# Motor_Controller_STM32.net
KiCad netlist of a schematic drawn in EasyEDA Pro
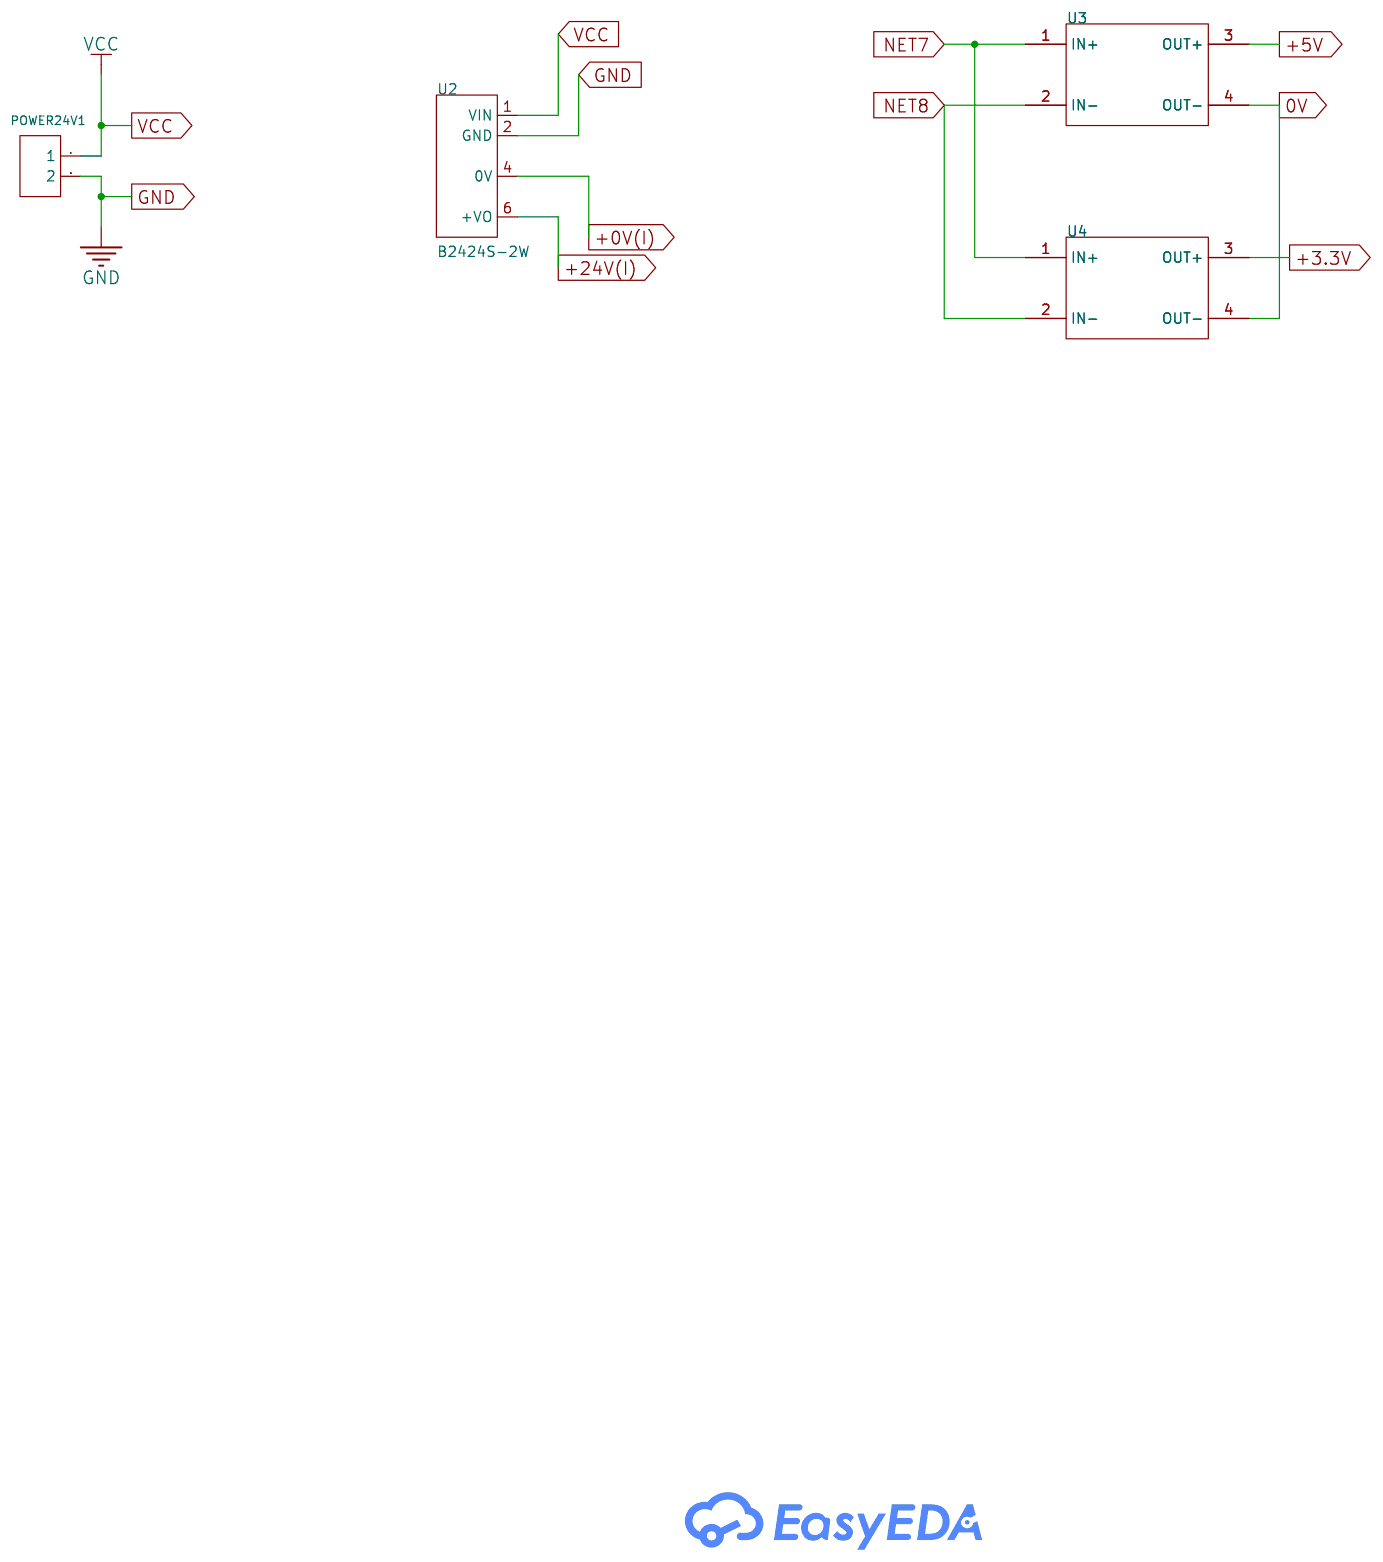
[diagram p0: schematic sheet]

(export (version "E")
  (design (tool "Eeschema 10.0.6"))
  (components
    (comp (ref "POWER24V1")
      (value "~")
      (footprint "easyedapro:HDR-TH_2P-P2.54-V-F")
      (libsource (lib "easyedapro") (part "Header-Female-2.54_1x2"))
    )
    (comp (ref "U2")
      (value "B2424S-2W")
      (footprint "easyedapro:PWRM-TH_BXXXXS-2W")
      (fields (field (name "Manufacturer") "JETEKPS(健特)"))
      (libsource (lib "easyedapro") (part "B2424S-2W_C442555"))
    )
    (comp (ref "U3")
      (value "~")
      (footprint "easyedapro:MINI 360")
      (libsource (lib "easyedapro") (part "Buck Converter Mini 360"))
    )
    (comp (ref "U4")
      (value "~")
      (footprint "easyedapro:MINI 360")
      (libsource (lib "easyedapro") (part "Buck Converter Mini 360"))
    )
  )
  (nets
    (net (code "1") (name "+0V(I)") (class "Default")
      (node (ref "U2") (pin "4") (pinfunction "0V_4") (pintype "unspecified"))
    )
    (net (code "2") (name "+3.3V") (class "Default")
      (node (ref "U4") (pin "3") (pinfunction "OUT+_3") (pintype "input"))
    )
    (net (code "3") (name "+5V") (class "Default")
      (node (ref "U3") (pin "3") (pinfunction "OUT+_3") (pintype "input"))
    )
    (net (code "4") (name "+24V(I)") (class "Default")
      (node (ref "U2") (pin "6") (pinfunction "+VO_6") (pintype "unspecified"))
    )
    (net (code "5") (name "0V") (class "Default")
      (node (ref "U3") (pin "4") (pinfunction "OUT-_4") (pintype "input"))
      (node (ref "U4") (pin "4") (pinfunction "OUT-_4") (pintype "input"))
    )
    (net (code "6") (name "GND") (class "Default")
      (node (ref "POWER24V1") (pin "2") (pinfunction "2_2") (pintype "input"))
      (node (ref "U2") (pin "2") (pinfunction "GND_2") (pintype "unspecified"))
    )
    (net (code "7") (name "NET7") (class "Default")
      (node (ref "U3") (pin "1") (pinfunction "IN+_1") (pintype "input"))
      (node (ref "U4") (pin "1") (pinfunction "IN+_1") (pintype "input"))
    )
    (net (code "8") (name "NET8") (class "Default")
      (node (ref "U3") (pin "2") (pinfunction "IN-_2") (pintype "input"))
      (node (ref "U4") (pin "2") (pinfunction "IN-_2") (pintype "input"))
    )
    (net (code "9") (name "VCC") (class "Default")
      (node (ref "POWER24V1") (pin "1") (pinfunction "1_1") (pintype "input"))
      (node (ref "U2") (pin "1") (pinfunction "VIN_1") (pintype "unspecified"))
    )
  )
)
